# Ticking_Sound_Generator.net
KiCad netlist of a schematic drawn in EAGLE
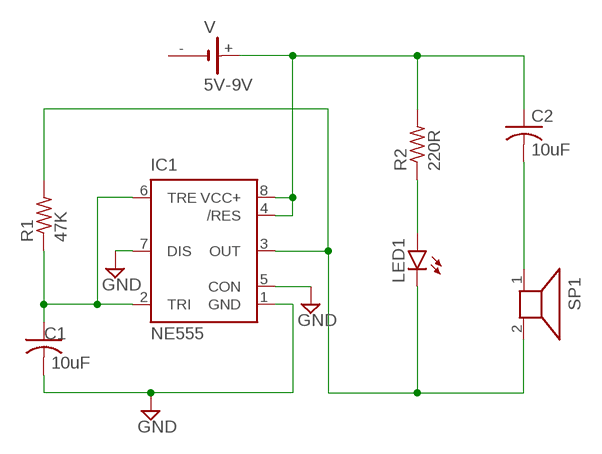
[diagram p0: schematic, sheet 1]

(export (version "E")
  (design (tool "Eeschema 10.0.6"))
  (components
    (comp (ref "C1")
      (value "10uF")
      (footprint "eagle-import:C025-024X044")
      (fields (field (name "SPICEPREFIX") "C") (field (name "SPICEPREFIX_1") "C1"))
      (libsource (lib "eagle-import") (part "C-US025-024X044"))
    )
    (comp (ref "C2")
      (value "10uF")
      (footprint "eagle-import:C025-024X044")
      (libsource (lib "eagle-import") (part "C-US025-024X044"))
    )
    (comp (ref "IC1")
      (value "NE555")
      (footprint "eagle-import:DIL-08")
      (fields (field (name "MF") "Arrow Electronics") (field (name "MPN") "NE555N"))
      (libsource (lib "eagle-import") (part "NE555"))
    )
    (comp (ref "LED1")
      (value "LAP4-BOTTOM")
      (footprint "eagle-import:P47F-BOTTOM")
      (libsource (lib "eagle-import") (part "P4-BOTTOMLA"))
    )
    (comp (ref "R1")
      (value "47K")
      (footprint "eagle-import:0204_7")
      (libsource (lib "eagle-import") (part "R-US_0204/7"))
    )
    (comp (ref "R2")
      (value "220R")
      (footprint "eagle-import:0204_7")
      (libsource (lib "eagle-import") (part "R-US_0204/7"))
    )
    (comp (ref "SP1")
      (value "AL23P")
      (footprint "eagle-import:AL23P")
      (libsource (lib "eagle-import") (part "AL23P"))
    )
    (comp (ref "V")
      (value "5V-9V")
      (footprint "eagle-import:SL-150-1_2AA_PT")
      (libsource (lib "eagle-import") (part "SL-150-1/2AA/PT"))
    )
  )
  (nets
    (net (code "1") (name "GND") (class "Default")
      (node (ref "C1") (pin "2") (pinfunction "2_2") (pintype "passive"))
      (node (ref "IC1") (pin "1") (pinfunction "GND_1") (pintype "power_in"))
      (node (ref "IC1") (pin "5") (pinfunction "CON_5") (pintype "input"))
      (node (ref "IC1") (pin "7") (pinfunction "DIS_7") (pintype "input"))
    )
    (net (code "2") (name "Net-(C2-Pad2)") (class "Default")
      (node (ref "C2") (pin "2") (pinfunction "2_2") (pintype "passive"))
      (node (ref "SP1") (pin "1") (pinfunction "1_1") (pintype "passive"))
    )
    (net (code "3") (name "Net-(IC1-OUT)") (class "Default")
      (node (ref "IC1") (pin "3") (pinfunction "OUT_3") (pintype "output"))
      (node (ref "LED1") (pin "C") (pinfunction "C_C") (pintype "passive"))
      (node (ref "R1") (pin "2") (pinfunction "2_2") (pintype "passive"))
      (node (ref "SP1") (pin "2") (pinfunction "2_2") (pintype "passive"))
    )
    (net (code "4") (name "Net-(IC1-TRE)") (class "Default")
      (node (ref "C1") (pin "1") (pinfunction "1_1") (pintype "passive"))
      (node (ref "IC1") (pin "2") (pinfunction "TRI_2") (pintype "input"))
      (node (ref "IC1") (pin "6") (pinfunction "TRE_6") (pintype "input"))
      (node (ref "R1") (pin "1") (pinfunction "1_1") (pintype "passive"))
    )
    (net (code "5") (name "Net-(IC1-VCC+)") (class "Default")
      (node (ref "C2") (pin "1") (pinfunction "1_1") (pintype "passive"))
      (node (ref "IC1") (pin "4") (pinfunction "/RES_4") (pintype "input"))
      (node (ref "IC1") (pin "8") (pinfunction "VCC+_8") (pintype "power_in"))
      (node (ref "R2") (pin "2") (pinfunction "2_2") (pintype "passive"))
      (node (ref "V") (pin "+") (pinfunction "+_+") (pintype "passive"))
    )
    (net (code "6") (name "Net-(LED1-PadA)") (class "Default")
      (node (ref "LED1") (pin "A") (pinfunction "A_A") (pintype "passive"))
      (node (ref "R2") (pin "1") (pinfunction "1_1") (pintype "passive"))
    )
    (net (code "7") (name "unconnected-(V---Pad-@1)") (class "Default")
      (node (ref "V") (pin "-@1") (pinfunction "-_-@1") (pintype "passive"))
    )
    (net (code "8") (name "unconnected-(V-Pad-)") (class "Default")
      (node (ref "V") (pin "-") (pinfunction "-_-") (pintype "passive"))
    )
  )
)
